# elec_-_pi_pico.net
KiCad netlist of a schematic drawn in EAGLE
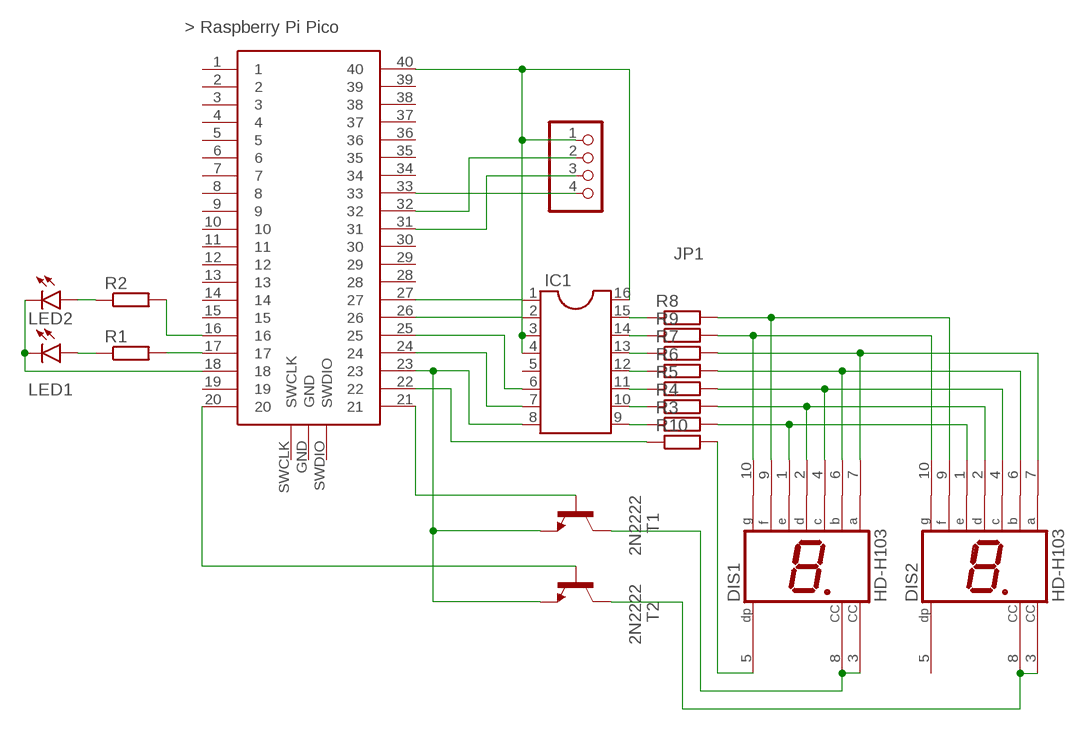
[diagram p0: schematic, sheet 1]

(export (version "E")
  (design (tool "Eeschema 10.0.6"))
  (components
    (comp (ref "DIS1")
      (value "HD-H103")
      (footprint "eagle-import:HDSP-M")
      (libsource (lib "eagle-import") (part "HD-H103"))
    )
    (comp (ref "DIS2")
      (value "HD-H103")
      (footprint "eagle-import:HDSP-M")
      (libsource (lib "eagle-import") (part "HD-H103"))
    )
    (comp (ref "IC1")
      (value "DIL16")
      (footprint "eagle-import:DIL16")
      (libsource (lib "eagle-import") (part "DIL16"))
    )
    (comp (ref "JP1")
      (value "PINHD-1X4")
      (footprint "eagle-import:1X04")
      (libsource (lib "eagle-import") (part "PINHD-1X4"))
    )
    (comp (ref "LED1")
      (value "LED5MM")
      (footprint "eagle-import:LED5MM")
      (libsource (lib "eagle-import") (part "LED5MM"))
    )
    (comp (ref "LED2")
      (value "LED5MM")
      (footprint "eagle-import:LED5MM")
      (libsource (lib "eagle-import") (part "LED5MM"))
    )
    (comp (ref "R1")
      (value "R-EU_0204/2V")
      (footprint "eagle-import:0204V")
      (libsource (lib "eagle-import") (part "R-EU_0204/2V"))
    )
    (comp (ref "R2")
      (value "R-EU_0204/2V")
      (footprint "eagle-import:0204V")
      (libsource (lib "eagle-import") (part "R-EU_0204/2V"))
    )
    (comp (ref "R3")
      (value "R-EU_0204/2V")
      (footprint "eagle-import:0204V")
      (libsource (lib "eagle-import") (part "R-EU_0204/2V"))
    )
    (comp (ref "R4")
      (value "R-EU_0204/2V")
      (footprint "eagle-import:0204V")
      (libsource (lib "eagle-import") (part "R-EU_0204/2V"))
    )
    (comp (ref "R5")
      (value "R-EU_0204/2V")
      (footprint "eagle-import:0204V")
      (libsource (lib "eagle-import") (part "R-EU_0204/2V"))
    )
    (comp (ref "R6")
      (value "R-EU_0204/2V")
      (footprint "eagle-import:0204V")
      (libsource (lib "eagle-import") (part "R-EU_0204/2V"))
    )
    (comp (ref "R7")
      (value "R-EU_0204/2V")
      (footprint "eagle-import:0204V")
      (libsource (lib "eagle-import") (part "R-EU_0204/2V"))
    )
    (comp (ref "R8")
      (value "R-EU_0204/2V")
      (footprint "eagle-import:0204V")
      (libsource (lib "eagle-import") (part "R-EU_0204/2V"))
    )
    (comp (ref "R9")
      (value "R-EU_0204/2V")
      (footprint "eagle-import:0204V")
      (libsource (lib "eagle-import") (part "R-EU_0204/2V"))
    )
    (comp (ref "R10")
      (value "R-EU_0204/2V")
      (footprint "eagle-import:0204V")
      (libsource (lib "eagle-import") (part "R-EU_0204/2V"))
    )
    (comp (ref "T1")
      (value "2N2222")
      (footprint "eagle-import:TO18")
      (libsource (lib "eagle-import") (part "2N2222"))
    )
    (comp (ref "T2")
      (value "2N2222")
      (footprint "eagle-import:TO18")
      (libsource (lib "eagle-import") (part "2N2222"))
    )
    (comp (ref "U$1")
      (value "RASPBERRY-PI-PICO_TH")
      (footprint "eagle-import:FT_RASPBERRY-PI-PICO_TH")
      (libsource (lib "eagle-import") (part "RASPBERRY-PI-PICO_TH"))
    )
  )
  (nets
    (net (code "1") (name "Net-(DIS1-A)") (class "Default")
      (node (ref "DIS1") (pin "7") (pinfunction "A_7") (pintype "passive"))
      (node (ref "DIS2") (pin "7") (pinfunction "A_7") (pintype "passive"))
      (node (ref "R7") (pin "2") (pinfunction "2_2") (pintype "passive"))
    )
    (net (code "2") (name "Net-(DIS1-B)") (class "Default")
      (node (ref "DIS1") (pin "6") (pinfunction "B_6") (pintype "passive"))
      (node (ref "DIS2") (pin "6") (pinfunction "B_6") (pintype "passive"))
      (node (ref "R6") (pin "2") (pinfunction "2_2") (pintype "passive"))
    )
    (net (code "3") (name "Net-(DIS1-C)") (class "Default")
      (node (ref "DIS1") (pin "4") (pinfunction "C_4") (pintype "passive"))
      (node (ref "DIS2") (pin "4") (pinfunction "C_4") (pintype "passive"))
      (node (ref "R5") (pin "2") (pinfunction "2_2") (pintype "passive"))
    )
    (net (code "4") (name "Net-(DIS1-D)") (class "Default")
      (node (ref "DIS1") (pin "2") (pinfunction "D_2") (pintype "passive"))
      (node (ref "DIS2") (pin "2") (pinfunction "D_2") (pintype "passive"))
      (node (ref "R4") (pin "2") (pinfunction "2_2") (pintype "passive"))
    )
    (net (code "5") (name "Net-(DIS1-DP)") (class "Default")
      (node (ref "DIS1") (pin "5") (pinfunction "DP_5") (pintype "passive"))
      (node (ref "R10") (pin "2") (pinfunction "2_2") (pintype "passive"))
    )
    (net (code "6") (name "Net-(DIS1-E)") (class "Default")
      (node (ref "DIS1") (pin "1") (pinfunction "E_1") (pintype "passive"))
      (node (ref "DIS2") (pin "1") (pinfunction "E_1") (pintype "passive"))
      (node (ref "R3") (pin "2") (pinfunction "2_2") (pintype "passive"))
    )
    (net (code "7") (name "Net-(DIS1-F)") (class "Default")
      (node (ref "DIS1") (pin "9") (pinfunction "F_9") (pintype "passive"))
      (node (ref "DIS2") (pin "9") (pinfunction "F_9") (pintype "passive"))
      (node (ref "R8") (pin "2") (pinfunction "2_2") (pintype "passive"))
    )
    (net (code "8") (name "Net-(DIS1-G)") (class "Default")
      (node (ref "DIS1") (pin "10") (pinfunction "G_10") (pintype "passive"))
      (node (ref "DIS2") (pin "10") (pinfunction "G_10") (pintype "passive"))
      (node (ref "R9") (pin "2") (pinfunction "2_2") (pintype "passive"))
    )
    (net (code "9") (name "Net-(IC1-Pad1)") (class "Default")
      (node (ref "IC1") (pin "1") (pinfunction "1_1") (pintype "passive"))
      (node (ref "U$1") (pin "27") (pinfunction "27_27") (pintype "bidirectional"))
    )
    (net (code "10") (name "Net-(IC1-Pad2)") (class "Default")
      (node (ref "IC1") (pin "2") (pinfunction "2_2") (pintype "passive"))
      (node (ref "U$1") (pin "26") (pinfunction "26_26") (pintype "bidirectional"))
    )
    (net (code "11") (name "Net-(IC1-Pad6)") (class "Default")
      (node (ref "IC1") (pin "6") (pinfunction "6_6") (pintype "passive"))
      (node (ref "U$1") (pin "25") (pinfunction "25_25") (pintype "bidirectional"))
    )
    (net (code "12") (name "Net-(IC1-Pad7)") (class "Default")
      (node (ref "IC1") (pin "7") (pinfunction "7_7") (pintype "passive"))
      (node (ref "U$1") (pin "24") (pinfunction "24_24") (pintype "bidirectional"))
    )
    (net (code "13") (name "Net-(IC1-Pad9)") (class "Default")
      (node (ref "IC1") (pin "9") (pinfunction "9_9") (pintype "passive"))
      (node (ref "R3") (pin "1") (pinfunction "1_1") (pintype "passive"))
    )
    (net (code "14") (name "Net-(IC1-Pad10)") (class "Default")
      (node (ref "IC1") (pin "10") (pinfunction "10_10") (pintype "passive"))
      (node (ref "R4") (pin "1") (pinfunction "1_1") (pintype "passive"))
    )
    (net (code "15") (name "Net-(IC1-Pad11)") (class "Default")
      (node (ref "IC1") (pin "11") (pinfunction "11_11") (pintype "passive"))
      (node (ref "R5") (pin "1") (pinfunction "1_1") (pintype "passive"))
    )
    (net (code "16") (name "Net-(IC1-Pad12)") (class "Default")
      (node (ref "IC1") (pin "12") (pinfunction "12_12") (pintype "passive"))
      (node (ref "R6") (pin "1") (pinfunction "1_1") (pintype "passive"))
    )
    (net (code "17") (name "Net-(IC1-Pad13)") (class "Default")
      (node (ref "IC1") (pin "13") (pinfunction "13_13") (pintype "passive"))
      (node (ref "R7") (pin "1") (pinfunction "1_1") (pintype "passive"))
    )
    (net (code "18") (name "Net-(IC1-Pad14)") (class "Default")
      (node (ref "IC1") (pin "14") (pinfunction "14_14") (pintype "passive"))
      (node (ref "R9") (pin "1") (pinfunction "1_1") (pintype "passive"))
    )
    (net (code "19") (name "Net-(IC1-Pad15)") (class "Default")
      (node (ref "IC1") (pin "15") (pinfunction "15_15") (pintype "passive"))
      (node (ref "R8") (pin "1") (pinfunction "1_1") (pintype "passive"))
    )
    (net (code "20") (name "Net-(IC1-Pad16)") (class "Default")
      (node (ref "IC1") (pin "16") (pinfunction "16_16") (pintype "passive"))
      (node (ref "IC1") (pin "3") (pinfunction "3_3") (pintype "passive"))
      (node (ref "IC1") (pin "4") (pinfunction "4_4") (pintype "passive"))
      (node (ref "JP1") (pin "1") (pinfunction "1_1") (pintype "passive"))
      (node (ref "U$1") (pin "40") (pinfunction "40_40") (pintype "bidirectional"))
    )
    (net (code "21") (name "Net-(JP1-Pad2)") (class "Default")
      (node (ref "JP1") (pin "2") (pinfunction "2_2") (pintype "passive"))
      (node (ref "U$1") (pin "32") (pinfunction "32_32") (pintype "bidirectional"))
    )
    (net (code "22") (name "Net-(JP1-Pad3)") (class "Default")
      (node (ref "JP1") (pin "3") (pinfunction "3_3") (pintype "passive"))
      (node (ref "U$1") (pin "31") (pinfunction "31_31") (pintype "bidirectional"))
    )
    (net (code "23") (name "Net-(JP1-Pad4)") (class "Default")
      (node (ref "JP1") (pin "4") (pinfunction "4_4") (pintype "passive"))
      (node (ref "U$1") (pin "33") (pinfunction "33_33") (pintype "bidirectional"))
    )
    (net (code "24") (name "Net-(LED1-C)") (class "Default")
      (node (ref "LED1") (pin "K") (pinfunction "C_K") (pintype "passive"))
      (node (ref "LED2") (pin "K") (pinfunction "C_K") (pintype "passive"))
      (node (ref "U$1") (pin "18") (pinfunction "18_18") (pintype "bidirectional"))
    )
    (net (code "25") (name "Net-(LED1-PadA)") (class "Default")
      (node (ref "LED1") (pin "A") (pinfunction "A_A") (pintype "passive"))
      (node (ref "R1") (pin "1") (pinfunction "1_1") (pintype "passive"))
    )
    (net (code "26") (name "Net-(LED2-PadA)") (class "Default")
      (node (ref "LED2") (pin "A") (pinfunction "A_A") (pintype "passive"))
      (node (ref "R2") (pin "1") (pinfunction "1_1") (pintype "passive"))
    )
    (net (code "27") (name "Net-(R1-Pad2)") (class "Default")
      (node (ref "R1") (pin "2") (pinfunction "2_2") (pintype "passive"))
      (node (ref "U$1") (pin "17") (pinfunction "17_17") (pintype "bidirectional"))
    )
    (net (code "28") (name "Net-(R2-Pad2)") (class "Default")
      (node (ref "R2") (pin "2") (pinfunction "2_2") (pintype "passive"))
      (node (ref "U$1") (pin "16") (pinfunction "16_16") (pintype "bidirectional"))
    )
    (net (code "29") (name "Net-(R10-Pad1)") (class "Default")
      (node (ref "R10") (pin "1") (pinfunction "1_1") (pintype "passive"))
      (node (ref "U$1") (pin "22") (pinfunction "22_22") (pintype "bidirectional"))
    )
    (net (code "30") (name "Net-(T1-B)") (class "Default")
      (node (ref "T1") (pin "2") (pinfunction "B_2") (pintype "passive"))
      (node (ref "U$1") (pin "21") (pinfunction "21_21") (pintype "bidirectional"))
    )
    (net (code "31") (name "Net-(T1-C)") (class "Default")
      (node (ref "DIS1") (pin "3") (pinfunction "CC_3") (pintype "passive"))
      (node (ref "DIS1") (pin "8") (pinfunction "CC_8") (pintype "passive"))
      (node (ref "T1") (pin "3") (pinfunction "C_3") (pintype "passive"))
    )
    (net (code "32") (name "Net-(T1-E)") (class "Default")
      (node (ref "IC1") (pin "8") (pinfunction "8_8") (pintype "passive"))
      (node (ref "T1") (pin "1") (pinfunction "E_1") (pintype "passive"))
      (node (ref "T2") (pin "1") (pinfunction "E_1") (pintype "passive"))
      (node (ref "U$1") (pin "23") (pinfunction "23_23") (pintype "bidirectional"))
    )
    (net (code "33") (name "Net-(T2-B)") (class "Default")
      (node (ref "T2") (pin "2") (pinfunction "B_2") (pintype "passive"))
      (node (ref "U$1") (pin "20") (pinfunction "20_20") (pintype "bidirectional"))
    )
    (net (code "34") (name "Net-(T2-C)") (class "Default")
      (node (ref "DIS2") (pin "3") (pinfunction "CC_3") (pintype "passive"))
      (node (ref "DIS2") (pin "8") (pinfunction "CC_8") (pintype "passive"))
      (node (ref "T2") (pin "3") (pinfunction "C_3") (pintype "passive"))
    )
    (net (code "35") (name "unconnected-(DIS2-DP-Pad5)") (class "Default")
      (node (ref "DIS2") (pin "5") (pinfunction "DP_5") (pintype "passive"))
    )
    (net (code "36") (name "unconnected-(IC1-Pad5)") (class "Default")
      (node (ref "IC1") (pin "5") (pinfunction "5_5") (pintype "passive"))
    )
    (net (code "37") (name "unconnected-(U$1-Pad1)") (class "Default")
      (node (ref "U$1") (pin "1") (pinfunction "1_1") (pintype "bidirectional"))
    )
    (net (code "38") (name "unconnected-(U$1-Pad2)") (class "Default")
      (node (ref "U$1") (pin "2") (pinfunction "2_2") (pintype "bidirectional"))
    )
    (net (code "39") (name "unconnected-(U$1-Pad3)") (class "Default")
      (node (ref "U$1") (pin "3") (pinfunction "3_3") (pintype "bidirectional"))
    )
    (net (code "40") (name "unconnected-(U$1-Pad4)") (class "Default")
      (node (ref "U$1") (pin "4") (pinfunction "4_4") (pintype "bidirectional"))
    )
    (net (code "41") (name "unconnected-(U$1-Pad5)") (class "Default")
      (node (ref "U$1") (pin "5") (pinfunction "5_5") (pintype "bidirectional"))
    )
    (net (code "42") (name "unconnected-(U$1-Pad6)") (class "Default")
      (node (ref "U$1") (pin "6") (pinfunction "6_6") (pintype "bidirectional"))
    )
    (net (code "43") (name "unconnected-(U$1-Pad7)") (class "Default")
      (node (ref "U$1") (pin "7") (pinfunction "7_7") (pintype "bidirectional"))
    )
    (net (code "44") (name "unconnected-(U$1-Pad8)") (class "Default")
      (node (ref "U$1") (pin "8") (pinfunction "8_8") (pintype "bidirectional"))
    )
    (net (code "45") (name "unconnected-(U$1-Pad9)") (class "Default")
      (node (ref "U$1") (pin "9") (pinfunction "9_9") (pintype "bidirectional"))
    )
    (net (code "46") (name "unconnected-(U$1-Pad10)") (class "Default")
      (node (ref "U$1") (pin "10") (pinfunction "10_10") (pintype "bidirectional"))
    )
    (net (code "47") (name "unconnected-(U$1-Pad11)") (class "Default")
      (node (ref "U$1") (pin "11") (pinfunction "11_11") (pintype "bidirectional"))
    )
    (net (code "48") (name "unconnected-(U$1-Pad12)") (class "Default")
      (node (ref "U$1") (pin "12") (pinfunction "12_12") (pintype "bidirectional"))
    )
    (net (code "49") (name "unconnected-(U$1-Pad13)") (class "Default")
      (node (ref "U$1") (pin "13") (pinfunction "13_13") (pintype "bidirectional"))
    )
    (net (code "50") (name "unconnected-(U$1-Pad14)") (class "Default")
      (node (ref "U$1") (pin "14") (pinfunction "14_14") (pintype "bidirectional"))
    )
    (net (code "51") (name "unconnected-(U$1-Pad15)") (class "Default")
      (node (ref "U$1") (pin "15") (pinfunction "15_15") (pintype "bidirectional"))
    )
    (net (code "52") (name "unconnected-(U$1-Pad19)") (class "Default")
      (node (ref "U$1") (pin "19") (pinfunction "19_19") (pintype "bidirectional"))
    )
    (net (code "53") (name "unconnected-(U$1-Pad28)") (class "Default")
      (node (ref "U$1") (pin "28") (pinfunction "28_28") (pintype "bidirectional"))
    )
    (net (code "54") (name "unconnected-(U$1-Pad29)") (class "Default")
      (node (ref "U$1") (pin "29") (pinfunction "29_29") (pintype "bidirectional"))
    )
    (net (code "55") (name "unconnected-(U$1-Pad30)") (class "Default")
      (node (ref "U$1") (pin "30") (pinfunction "30_30") (pintype "bidirectional"))
    )
    (net (code "56") (name "unconnected-(U$1-Pad34)") (class "Default")
      (node (ref "U$1") (pin "34") (pinfunction "34_34") (pintype "bidirectional"))
    )
    (net (code "57") (name "unconnected-(U$1-Pad35)") (class "Default")
      (node (ref "U$1") (pin "35") (pinfunction "35_35") (pintype "bidirectional"))
    )
    (net (code "58") (name "unconnected-(U$1-Pad36)") (class "Default")
      (node (ref "U$1") (pin "36") (pinfunction "36_36") (pintype "bidirectional"))
    )
    (net (code "59") (name "unconnected-(U$1-Pad37)") (class "Default")
      (node (ref "U$1") (pin "37") (pinfunction "37_37") (pintype "bidirectional"))
    )
    (net (code "60") (name "unconnected-(U$1-Pad38)") (class "Default")
      (node (ref "U$1") (pin "38") (pinfunction "38_38") (pintype "bidirectional"))
    )
    (net (code "61") (name "unconnected-(U$1-Pad39)") (class "Default")
      (node (ref "U$1") (pin "39") (pinfunction "39_39") (pintype "bidirectional"))
    )
    (net (code "62") (name "unconnected-(U$1-PadGND)") (class "Default")
      (node (ref "U$1") (pin "GND") (pinfunction "GND_GND") (pintype "bidirectional"))
    )
    (net (code "63") (name "unconnected-(U$1-PadSWCLK)") (class "Default")
      (node (ref "U$1") (pin "SWCLK") (pinfunction "SWCLK_SWCLK") (pintype "bidirectional"))
    )
    (net (code "64") (name "unconnected-(U$1-PadSWDIO)") (class "Default")
      (node (ref "U$1") (pin "SWDIO") (pinfunction "SWDIO_SWDIO") (pintype "bidirectional"))
    )
  )
)
